# humidifier.net
KiCad netlist of a schematic drawn in EAGLE
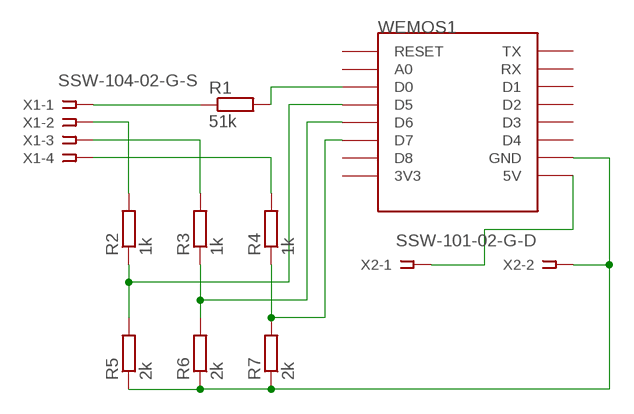
[diagram p0: schematic, sheet 1]

(export (version "E")
  (design (tool "Eeschema 10.0.6"))
  (components
    (comp (ref "R1")
      (value "51k")
      (footprint "eagle-import:R1206")
      (libsource (lib "eagle-import") (part "R-EU_R1206"))
    )
    (comp (ref "R2")
      (value "1k")
      (footprint "eagle-import:R1206")
      (libsource (lib "eagle-import") (part "R-EU_R1206"))
    )
    (comp (ref "R3")
      (value "1k")
      (footprint "eagle-import:R1206")
      (libsource (lib "eagle-import") (part "R-EU_R1206"))
    )
    (comp (ref "R4")
      (value "1k")
      (footprint "eagle-import:R1206")
      (libsource (lib "eagle-import") (part "R-EU_R1206"))
    )
    (comp (ref "R5")
      (value "2k")
      (footprint "eagle-import:R1206")
      (libsource (lib "eagle-import") (part "R-EU_R1206"))
    )
    (comp (ref "R6")
      (value "2k")
      (footprint "eagle-import:R1206")
      (libsource (lib "eagle-import") (part "R-EU_R1206"))
    )
    (comp (ref "R7")
      (value "2k")
      (footprint "eagle-import:R1206")
      (libsource (lib "eagle-import") (part "R-EU_R1206"))
    )
    (comp (ref "WEMOS1")
      (value "WEMOS-D1-MINI")
      (footprint "eagle-import:WEMOS-D1-MINI")
      (libsource (lib "eagle-import") (part "WEMOS-D1-MINI"))
    )
    (comp (ref "X1")
      (value "SSW-104-02-G-S")
      (footprint "eagle-import:SSW-104-02-G-S")
      (fields (field (name "MF") "Samtec Inc."))
      (libsource (lib "eagle-import") (part "SSW-104-02-G-S"))
    )
    (comp (ref "X2")
      (value "SSW-101-02-G-D")
      (footprint "eagle-import:SSW-101-02-G-D")
      (fields (field (name "MF") "Samtec Inc."))
      (libsource (lib "eagle-import") (part "SSW-101-02-G-D"))
    )
  )
  (nets
    (net (code "1") (name "Net-(R1-Pad1)") (class "Default")
      (node (ref "R1") (pin "1") (pinfunction "1_1") (pintype "passive"))
      (node (ref "X1") (pin "1") (pinfunction "1_1") (pintype "passive"))
    )
    (net (code "2") (name "Net-(R1-Pad2)") (class "Default")
      (node (ref "R1") (pin "2") (pinfunction "2_2") (pintype "passive"))
      (node (ref "WEMOS1") (pin "D0") (pinfunction "D0_D0") (pintype "bidirectional"))
    )
    (net (code "3") (name "Net-(R2-Pad1)") (class "Default")
      (node (ref "R2") (pin "1") (pinfunction "1_1") (pintype "passive"))
      (node (ref "R5") (pin "2") (pinfunction "2_2") (pintype "passive"))
      (node (ref "WEMOS1") (pin "D5") (pinfunction "D5_D5") (pintype "bidirectional"))
    )
    (net (code "4") (name "Net-(R3-Pad1)") (class "Default")
      (node (ref "R3") (pin "1") (pinfunction "1_1") (pintype "passive"))
      (node (ref "R6") (pin "2") (pinfunction "2_2") (pintype "passive"))
      (node (ref "WEMOS1") (pin "D6") (pinfunction "D6_D6") (pintype "bidirectional"))
    )
    (net (code "5") (name "Net-(R4-Pad1)") (class "Default")
      (node (ref "R4") (pin "1") (pinfunction "1_1") (pintype "passive"))
      (node (ref "R7") (pin "2") (pinfunction "2_2") (pintype "passive"))
      (node (ref "WEMOS1") (pin "D7") (pinfunction "D7_D7") (pintype "bidirectional"))
    )
    (net (code "6") (name "Net-(WEMOS1-Pad5V)") (class "Default")
      (node (ref "WEMOS1") (pin "5V") (pinfunction "5V_5V") (pintype "bidirectional"))
      (node (ref "X2") (pin "1") (pinfunction "1_1") (pintype "passive"))
    )
    (net (code "7") (name "Net-(X1B-1)") (class "Default")
      (node (ref "R2") (pin "2") (pinfunction "2_2") (pintype "passive"))
      (node (ref "X1") (pin "2") (pinfunction "1_2") (pintype "passive"))
    )
    (net (code "8") (name "Net-(X1C-1)") (class "Default")
      (node (ref "R3") (pin "2") (pinfunction "2_2") (pintype "passive"))
      (node (ref "X1") (pin "3") (pinfunction "1_3") (pintype "passive"))
    )
    (net (code "9") (name "Net-(X1D-1)") (class "Default")
      (node (ref "R4") (pin "2") (pinfunction "2_2") (pintype "passive"))
      (node (ref "X1") (pin "4") (pinfunction "1_4") (pintype "passive"))
    )
    (net (code "10") (name "Net-(X2B-1)") (class "Default")
      (node (ref "R5") (pin "1") (pinfunction "1_1") (pintype "passive"))
      (node (ref "R6") (pin "1") (pinfunction "1_1") (pintype "passive"))
      (node (ref "R7") (pin "1") (pinfunction "1_1") (pintype "passive"))
      (node (ref "WEMOS1") (pin "GND") (pinfunction "GND_GND") (pintype "bidirectional"))
      (node (ref "X2") (pin "2") (pinfunction "1_2") (pintype "passive"))
    )
    (net (code "11") (name "unconnected-(WEMOS1-Pad3V3)") (class "Default")
      (node (ref "WEMOS1") (pin "3V3") (pinfunction "3V3_3V3") (pintype "bidirectional"))
    )
    (net (code "12") (name "unconnected-(WEMOS1-PadA0)") (class "Default")
      (node (ref "WEMOS1") (pin "A0") (pinfunction "A0_A0") (pintype "bidirectional"))
    )
    (net (code "13") (name "unconnected-(WEMOS1-PadD1)") (class "Default")
      (node (ref "WEMOS1") (pin "D1") (pinfunction "D1_D1") (pintype "bidirectional"))
    )
    (net (code "14") (name "unconnected-(WEMOS1-PadD2)") (class "Default")
      (node (ref "WEMOS1") (pin "D2") (pinfunction "D2_D2") (pintype "bidirectional"))
    )
    (net (code "15") (name "unconnected-(WEMOS1-PadD3)") (class "Default")
      (node (ref "WEMOS1") (pin "D3") (pinfunction "D3_D3") (pintype "bidirectional"))
    )
    (net (code "16") (name "unconnected-(WEMOS1-PadD4)") (class "Default")
      (node (ref "WEMOS1") (pin "D4") (pinfunction "D4_D4") (pintype "bidirectional"))
    )
    (net (code "17") (name "unconnected-(WEMOS1-PadD8)") (class "Default")
      (node (ref "WEMOS1") (pin "D8") (pinfunction "D8_D8") (pintype "bidirectional"))
    )
    (net (code "18") (name "unconnected-(WEMOS1-PadRESET)") (class "Default")
      (node (ref "WEMOS1") (pin "RESET") (pinfunction "RESET_RESET") (pintype "bidirectional"))
    )
    (net (code "19") (name "unconnected-(WEMOS1-PadRX)") (class "Default")
      (node (ref "WEMOS1") (pin "RX") (pinfunction "RX_RX") (pintype "bidirectional"))
    )
    (net (code "20") (name "unconnected-(WEMOS1-PadTX)") (class "Default")
      (node (ref "WEMOS1") (pin "TX") (pinfunction "TX_TX") (pintype "bidirectional"))
    )
  )
)
